# Controller.net
KiCad netlist of a schematic drawn in Altium Designer
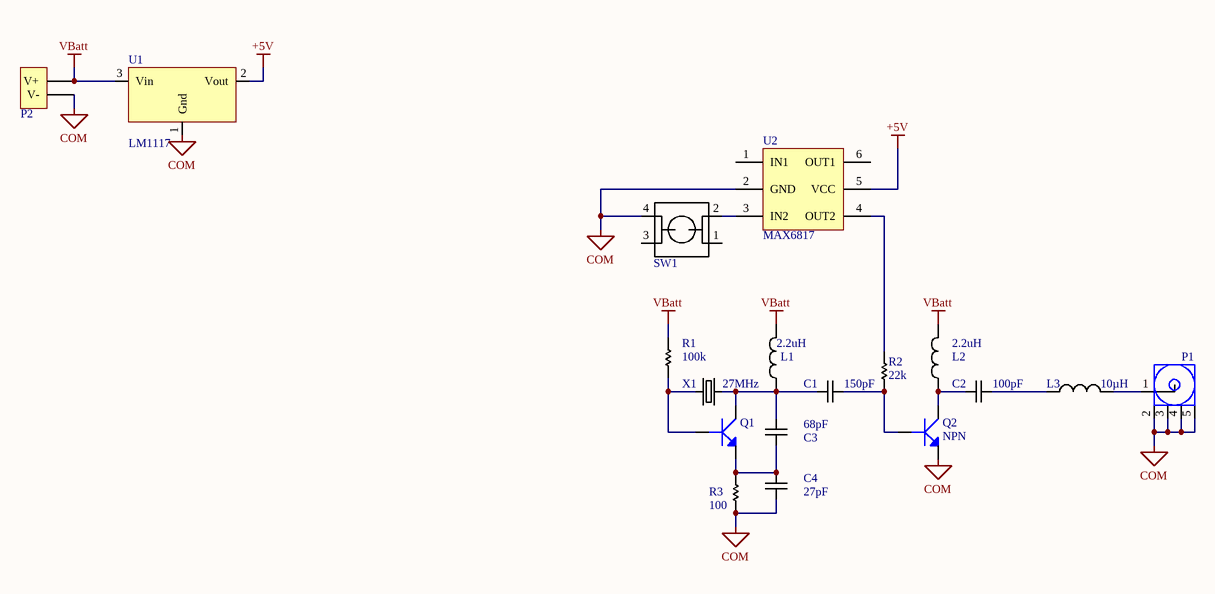
[diagram p0: Controller.SchDoc]

(export (version "E")
  (design (tool "Eeschema 10.0.6"))
  (components
    (comp (ref "C1")
      (value "150pF")
      (footprint "0805 - Cap Non-Polarized")
      (description "CAP CER 150PF 250V 5% NP0 0603")
      (fields
        (field (name "PART NUMBER") "Cap-TDK-CGA-150pF-0805")
        (field (name "MANUFACTURER") "TDK")
        (field (name "CREATED BY") "Pier-Yves")
      )
      (libsource (lib "local") (part "Cap"))
    )
    (comp (ref "C2")
      (value "100pF")
      (footprint "0805 - Cap Non-Polarized")
      (description "CAP CER 100PF 100V 5% NP0 0805")
      (fields
        (field (name "PART NUMBER") "Cap-TDK-CGA-100pF-0805")
        (field (name "MANUFACTURER") "TDK")
        (field (name "CREATED BY") "Pier-Yves")
      )
      (libsource (lib "local") (part "Cap"))
    )
    (comp (ref "C3")
      (value "68pF")
      (footprint "0805 - Cap Non-Polarized")
      (description "CAP CER 68PF 100V 5% NP0 0603")
      (fields
        (field (name "PART NUMBER") "Cap-TDK-CGA-68pF-0805")
        (field (name "MANUFACTURER") "TDK")
        (field (name "CREATED BY") "Pier-Yves")
      )
      (libsource (lib "local") (part "Cap"))
    )
    (comp (ref "C4")
      (value "27pF")
      (footprint "0805 - Cap Non-Polarized")
      (description "CAP CER 27PF 50V 5% NP0 0603")
      (fields
        (field (name "PART NUMBER") "Cap-TDK-CGA-27pF-0805")
        (field (name "MANUFACTURER") "TDK")
        (field (name "CREATED BY") "Pier-Yves")
      )
      (libsource (lib "local") (part "Cap"))
    )
    (comp (ref "L1")
      (value "2.2uH")
      (footprint "1008 - INDUCTOR")
      (description "IND 2200NH 280MA SRF 130MHZ 1008")
      (fields
        (field (name "PART NUMBER") "Murata-LQW2UA-Ind-AirCore-2.2uH")
        (field (name "MANUFACTURER") "Murata Electronics North America")
        (field (name "CREATED BY") "Frederic")
      )
      (libsource (lib "local") (part "Inductor"))
    )
    (comp (ref "L2")
      (value "2.2uH")
      (footprint "1008 - INDUCTOR")
      (description "IND 2200NH 280MA SRF 130MHZ 1008")
      (fields
        (field (name "PART NUMBER") "Murata-LQW2UA-Ind-AirCore-2.2uH")
        (field (name "MANUFACTURER") "Murata Electronics North America")
        (field (name "CREATED BY") "Frederic")
      )
      (libsource (lib "local") (part "Inductor"))
    )
    (comp (ref "L3")
      (value "10µH")
      (footprint "1812 - Inductor")
      (description "INDUCTOR 10 UH 5% 1812 SMD")
      (fields
        (field (name "PART NUMBER") "Ind-Panasonic-FB-10µH-1812")
        (field (name "MANUFACTURER") "Panasonic Electronic Components")
        (field (name "CREATED BY") "Pier-Yves")
      )
      (libsource (lib "local") (part "Inductor"))
    )
    (comp (ref "P1")
      (value "Coax-F")
      (footprint "SMA-Female-R/A-THT")
      (description "CONN SMA JACK R/A 50 OHM PCB")
      (fields
        (field (name "PART NUMBER") "coax-sma-ra-tht")
        (field (name "MANUFACTURER") "Linx Technologies Inc.")
        (field (name "CREATED BY") "Pier-Yves")
      )
      (libsource (lib "local") (part "COAX-F"))
    )
    (comp (ref "P2")
      (value "Battery Holder")
      (footprint "Battery Holder - 9V - THT")
      (description "HOLDER BATTERY 9V PC MOUNT")
      (fields
        (field (name "PART NUMBER") "Battery Holder-9V-THT-Open")
        (field (name "MANUFACTURER") "MPD")
        (field (name "CREATED BY") "Pier-Yves")
      )
      (libsource (lib "local") (part "Battery Holder - 2 pin"))
    )
    (comp (ref "Q1")
      (value "NPN")
      (footprint "SOT23-3")
      (description "TRANS NPN 40V 350MW SMD SOT23-3")
      (fields
        (field (name "PART NUMBER") "MMBT2222A-7-F")
        (field (name "MANUFACTURER") "Diodes Inc.")
        (field (name "CREATED BY") "Pier-Yves")
      )
      (libsource (lib "local") (part "BJT_NPN_BEC"))
    )
    (comp (ref "Q2")
      (value "NPN")
      (footprint "SOT23-3")
      (description "TRANS NPN 40V 350MW SMD SOT23-3")
      (fields
        (field (name "PART NUMBER") "MMBT2222A-7-F")
        (field (name "MANUFACTURER") "Diodes Inc.")
        (field (name "CREATED BY") "Pier-Yves")
      )
      (libsource (lib "local") (part "BJT_NPN_BEC"))
    )
    (comp (ref "R1")
      (value "100k")
      (footprint "0805 - Resistor")
      (description "RES 100K OHM 1/8W 5% 0805 SMD")
      (fields
        (field (name "PART NUMBER") "Yagao-RC0805-100k")
        (field (name "MANUFACTURER") "Yagao")
        (field (name "CREATED BY") "Pier-Yves")
      )
      (libsource (lib "local") (part "Res"))
    )
    (comp (ref "R2")
      (value "22k")
      (footprint "0805 - Resistor")
      (description "RES 22K OHM 1/8W 5% 0805 SMD")
      (fields
        (field (name "PART NUMBER") "Yagao-RC0805-22k")
        (field (name "MANUFACTURER") "Yagao")
        (field (name "CREATED BY") "Pier-Yves")
      )
      (libsource (lib "local") (part "Res"))
    )
    (comp (ref "R3")
      (value "100")
      (footprint "0805 - Resistor")
      (description "RES 100 OHM 1/8W 5% 0805 SMD")
      (fields
        (field (name "PART NUMBER") "Yagao-RC0805-100")
        (field (name "MANUFACTURER") "Yagao")
        (field (name "CREATED BY") "Pier-Yves")
      )
      (libsource (lib "local") (part "Res"))
    )
    (comp (ref "SW1")
      (value "Tact Switch")
      (footprint "TE FSMJSMA")
      (description "SWITCH TACTILE SPST-NO 0.05A 12V")
      (fields
        (field (name "PART NUMBER") "TactSwitch-SMD-Vertical-GullWing-6x6")
        (field (name "MANUFACTURER") "TE Connectivity")
        (field (name "CREATED BY") "Pier-Yves")
      )
      (libsource (lib "local") (part "Tact Switch"))
    )
    (comp (ref "U1")
      (value "LM1117")
      (footprint "SOT223-3")
      (description "Regulator LDO 5V")
      (fields
        (field (name "PART NUMBER") "LM1117 5v SOT223-3")
        (field (name "MANUFACTURER") "Texas Instrument")
        (field (name "CREATED BY") "Pier-Yves")
      )
      (libsource (lib "local") (part "LM1117"))
    )
    (comp (ref "U2")
      (value "MAX6817")
      (footprint "SOT23-6")
      (description "IC DEBOUNCER SWITCH DUAL SOT23-6")
      (fields (field (name "MANUFACTURER") "Maxim Integrated") (field (name "CREATED BY") "Pier-Yves"))
      (libsource (lib "local") (part "MAX6817"))
    )
    (comp (ref "X1")
      (value "27MHz")
      (footprint "HC49US")
      (description "CRYSTAL 27MHZ 18PF SMD")
      (fields
        (field (name "PART NUMBER") "TXC-9C-27MHz")
        (field (name "MANUFACTURER") "TXC CORPORATION")
        (field (name "CREATED BY") "Frederic")
      )
      (libsource (lib "local") (part "HC49US"))
    )
  )
  (nets
    (net (code "1") (name "+5V") (class "Default")
      (node (ref "U1") (pin "2") (pinfunction "Vout_2") (pintype "passive"))
      (node (ref "U2") (pin "5") (pinfunction "VCC_5") (pintype "passive"))
    )
    (net (code "2") (name "COM") (class "Default")
      (node (ref "C4") (pin "1") (pinfunction "1_1") (pintype "passive"))
      (node (ref "P1") (pin "2") (pinfunction "GND_2") (pintype "passive"))
      (node (ref "P1") (pin "3") (pinfunction "GND_3") (pintype "passive"))
      (node (ref "P1") (pin "4") (pinfunction "GND_4") (pintype "passive"))
      (node (ref "P1") (pin "5") (pinfunction "GND_5") (pintype "passive"))
      (node (ref "P2") (pin "2") (pinfunction "V-_2") (pintype "passive"))
      (node (ref "Q2") (pin "2") (pinfunction "E_2") (pintype "passive"))
      (node (ref "R3") (pin "1") (pinfunction "1_1") (pintype "passive"))
      (node (ref "SW1") (pin "4") (pinfunction "4_4") (pintype "passive"))
      (node (ref "U1") (pin "1") (pinfunction "Gnd_1") (pintype "passive"))
      (node (ref "U2") (pin "2") (pinfunction "GND_2") (pintype "passive"))
    )
    (net (code "3") (name "Net-(C2-Pad2)") (class "Default")
      (node (ref "C2") (pin "2") (pinfunction "2_2") (pintype "passive"))
      (node (ref "L3") (pin "1") (pinfunction "1_1") (pintype "passive"))
    )
    (net (code "4") (name "Net-(P1-Signal)") (class "Default")
      (node (ref "L3") (pin "2") (pinfunction "2_2") (pintype "passive"))
      (node (ref "P1") (pin "1") (pinfunction "Signal_1") (pintype "passive"))
    )
    (net (code "5") (name "Net-(Q1-B)") (class "Default")
      (node (ref "Q1") (pin "1") (pinfunction "B_1") (pintype "passive"))
      (node (ref "R1") (pin "1") (pinfunction "1_1") (pintype "passive"))
      (node (ref "X1") (pin "1") (pintype "passive"))
    )
    (net (code "6") (name "Net-(Q1-C)") (class "Default")
      (node (ref "C1") (pin "1") (pinfunction "1_1") (pintype "passive"))
      (node (ref "C3") (pin "2") (pinfunction "2_2") (pintype "passive"))
      (node (ref "L1") (pin "1") (pinfunction "1_1") (pintype "passive"))
      (node (ref "Q1") (pin "3") (pinfunction "C_3") (pintype "passive"))
      (node (ref "X1") (pin "2") (pintype "passive"))
    )
    (net (code "7") (name "Net-(Q1-E)") (class "Default")
      (node (ref "C3") (pin "1") (pinfunction "1_1") (pintype "passive"))
      (node (ref "C4") (pin "2") (pinfunction "2_2") (pintype "passive"))
      (node (ref "Q1") (pin "2") (pinfunction "E_2") (pintype "passive"))
      (node (ref "R3") (pin "2") (pinfunction "2_2") (pintype "passive"))
    )
    (net (code "8") (name "Net-(Q2-B)") (class "Default")
      (node (ref "C1") (pin "2") (pinfunction "2_2") (pintype "passive"))
      (node (ref "Q2") (pin "1") (pinfunction "B_1") (pintype "passive"))
      (node (ref "R2") (pin "1") (pinfunction "1_1") (pintype "passive"))
    )
    (net (code "9") (name "Net-(Q2-C)") (class "Default")
      (node (ref "C2") (pin "1") (pinfunction "1_1") (pintype "passive"))
      (node (ref "L2") (pin "1") (pinfunction "1_1") (pintype "passive"))
      (node (ref "Q2") (pin "3") (pinfunction "C_3") (pintype "passive"))
    )
    (net (code "10") (name "Net-(U2-IN2)") (class "Default")
      (node (ref "SW1") (pin "2") (pinfunction "2_2") (pintype "passive"))
      (node (ref "U2") (pin "3") (pinfunction "IN2_3") (pintype "passive"))
    )
    (net (code "11") (name "Net-(U2-OUT2)") (class "Default")
      (node (ref "R2") (pin "2") (pinfunction "2_2") (pintype "passive"))
      (node (ref "U2") (pin "4") (pinfunction "OUT2_4") (pintype "passive"))
    )
    (net (code "12") (name "VBatt") (class "Default")
      (node (ref "L1") (pin "2") (pinfunction "2_2") (pintype "passive"))
      (node (ref "L2") (pin "2") (pinfunction "2_2") (pintype "passive"))
      (node (ref "P2") (pin "1") (pinfunction "V+_1") (pintype "passive"))
      (node (ref "R1") (pin "2") (pinfunction "2_2") (pintype "passive"))
      (node (ref "U1") (pin "3") (pinfunction "Vin_3") (pintype "passive"))
    )
    (net (code "13") (name "unconnected-(SW1-Pad1)") (class "Default")
      (node (ref "SW1") (pin "1") (pinfunction "1_1") (pintype "passive"))
    )
    (net (code "14") (name "unconnected-(SW1-Pad3)") (class "Default")
      (node (ref "SW1") (pin "3") (pinfunction "3_3") (pintype "passive"))
    )
    (net (code "15") (name "unconnected-(U2-IN1-Pad1)") (class "Default")
      (node (ref "U2") (pin "1") (pinfunction "IN1_1") (pintype "passive"))
    )
    (net (code "16") (name "unconnected-(U2-OUT1-Pad6)") (class "Default")
      (node (ref "U2") (pin "6") (pinfunction "OUT1_6") (pintype "passive"))
    )
  )
)
